# PCB_PCB_NFC-Llamacard_2024-08-03.net
KiCad netlist of a schematic drawn in EasyEDA
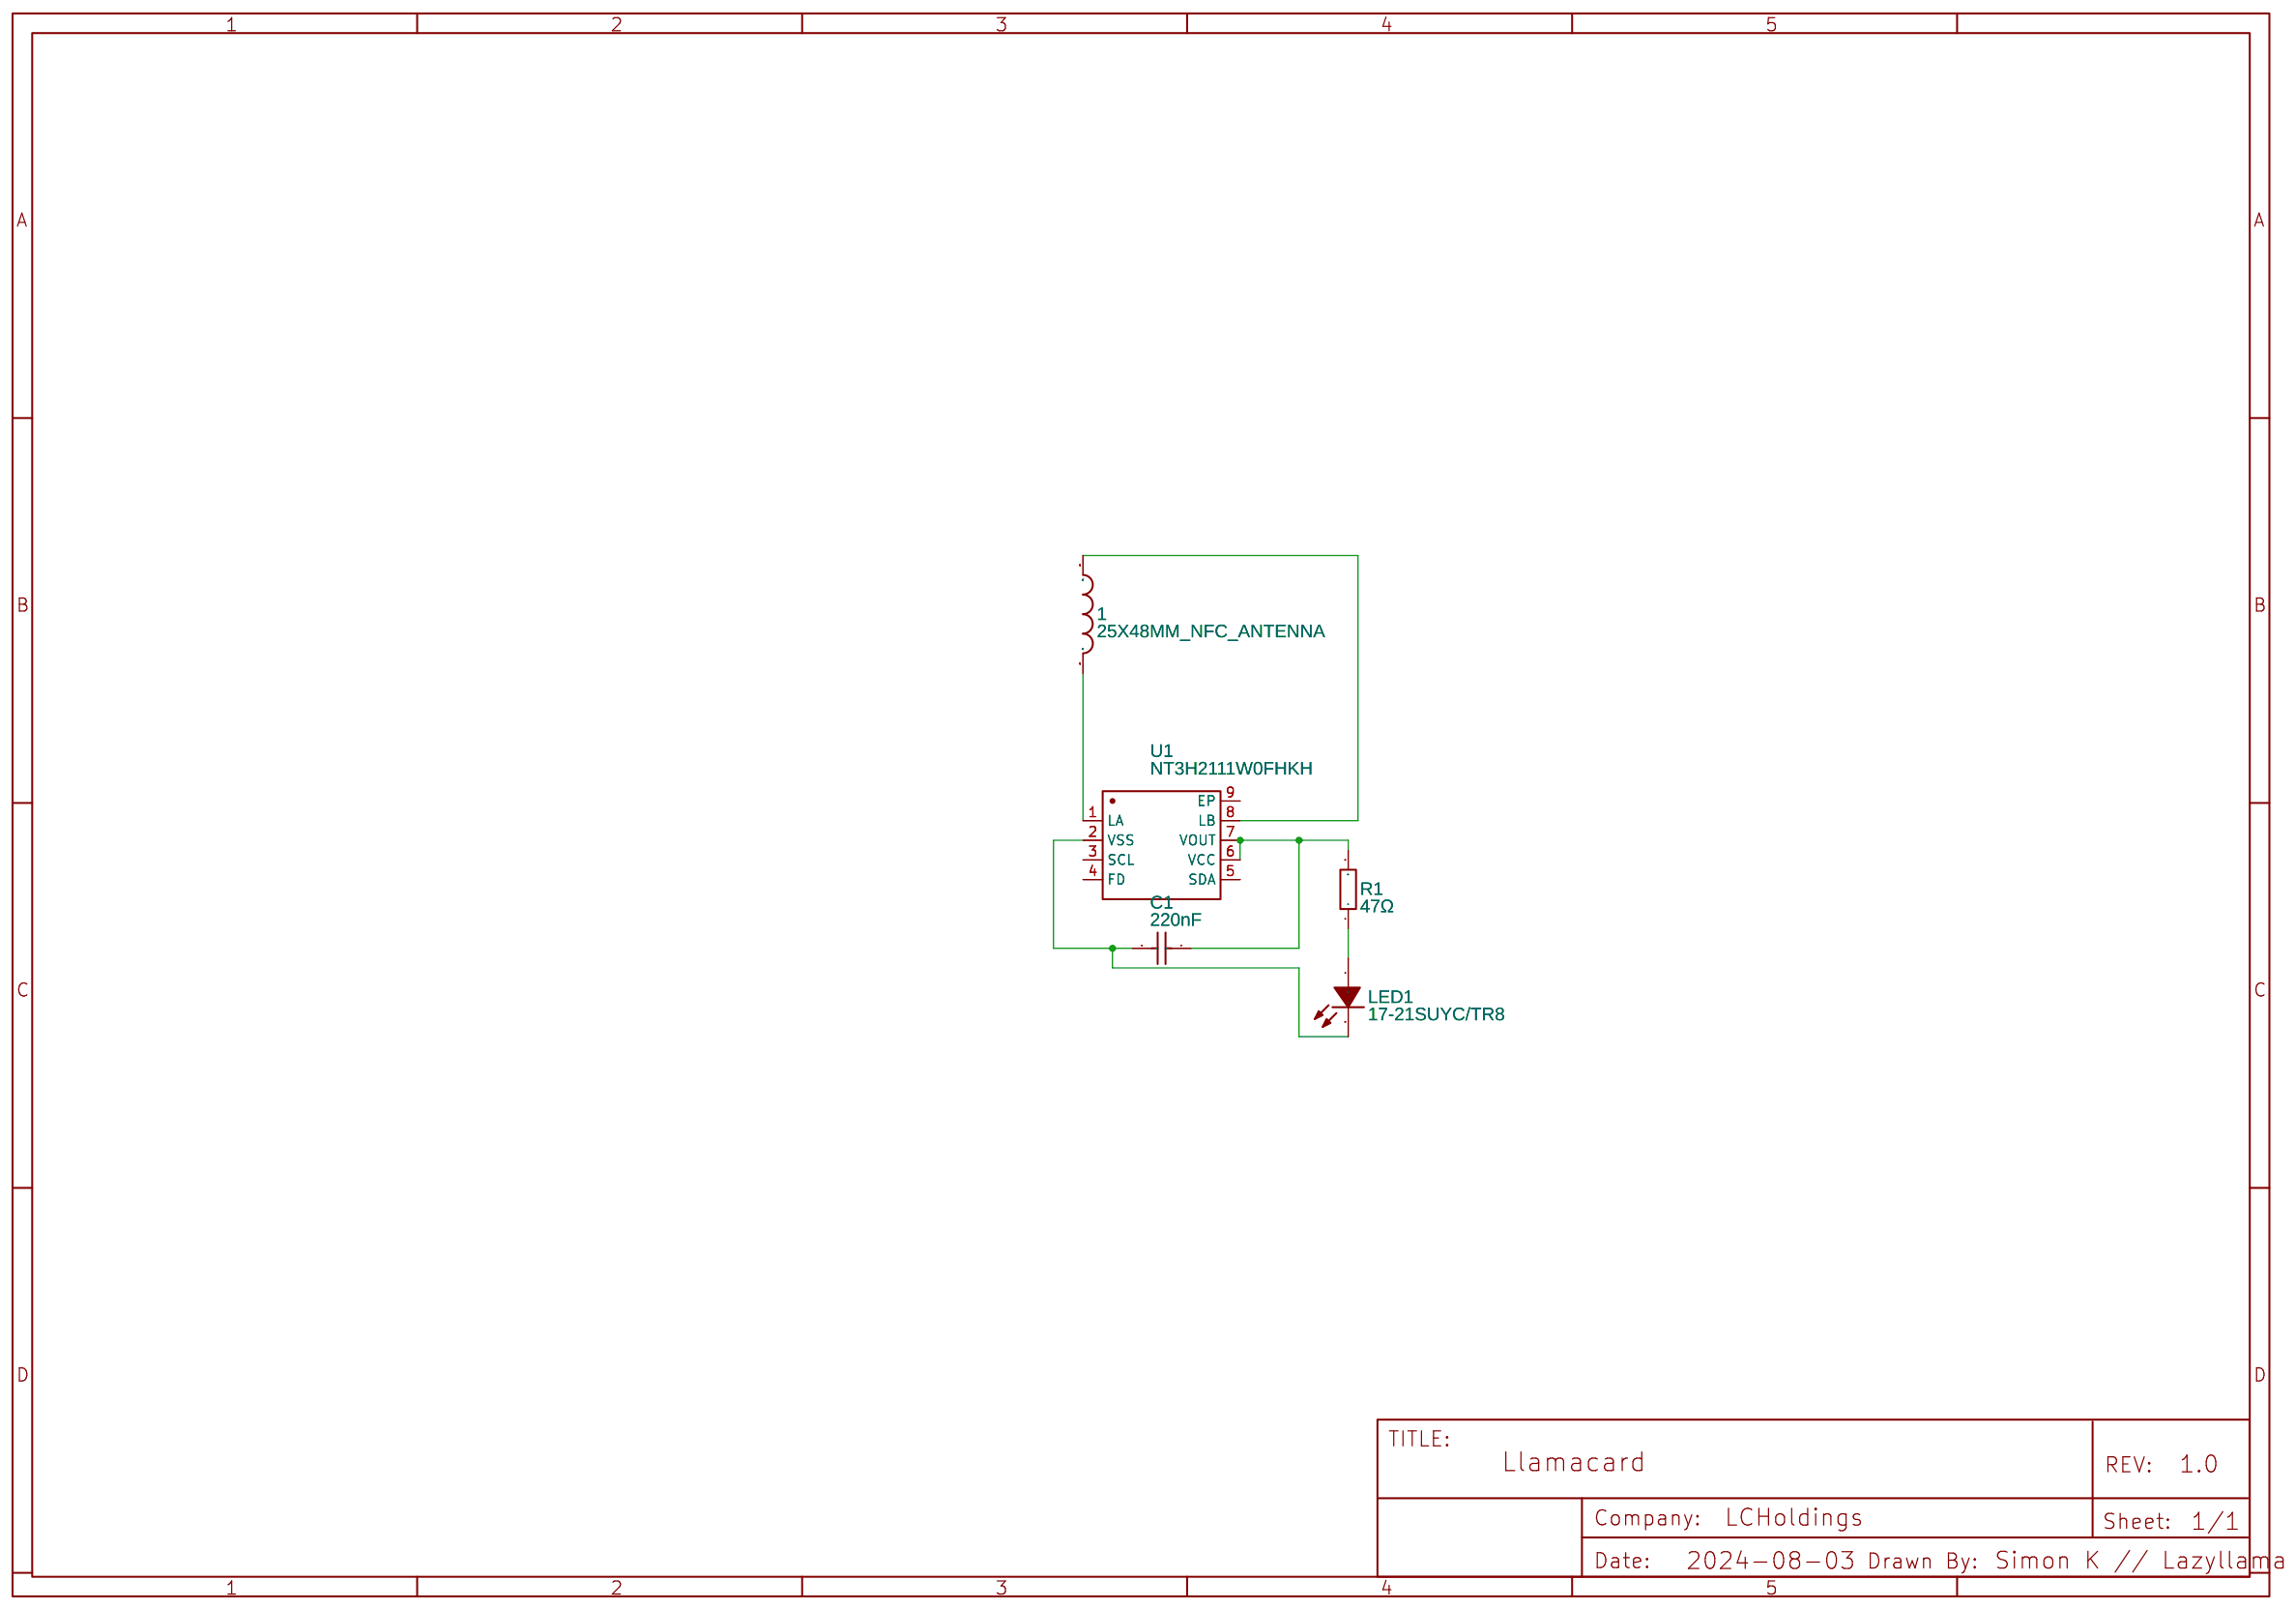
[diagram p0: schematic sheet]

(export (version "E")
  (design (tool "Eeschema 10.0.6"))
  (components
    (comp (ref "1") (value "25X48MM_NFC_ANTENNA") (libsource (lib "") (part "25X48MM_NFC_ANTENNA")))
    (comp (ref "C1")
      (value "220nF")
      (fields
        (field (name "Manufacturer Part") "CL10B224KA8NNNC")
        (field (name "Manufacturer") "SAMSUNG(三星)")
      )
      (libsource (lib "") (part "CL10B224KA8NNNC"))
    )
    (comp (ref "LED1")
      (value "17-21SUYC/TR8")
      (fields (field (name "Manufacturer Part") "KT-0805黄灯") (field (name "Manufacturer") "KENTO"))
      (libsource (lib "") (part "17-21SUYC/TR8"))
    )
    (comp (ref "R1")
      (value "47Ω")
      (fields
        (field (name "Manufacturer Part") "0603WAF470JT5E")
        (field (name "Manufacturer") "UNI-ROYAL(厚声)")
      )
      (libsource (lib "") (part "0603WAF470JT5E"))
    )
    (comp (ref "U1")
      (value "NT3H2111W0FHKH")
      (fields (field (name "Manufacturer") "NXP(恩智浦)"))
      (libsource (lib "") (part "NT3H2111W0FHKH"))
    )
  )
  (nets
    (net (code "1") (name "Net-(LED1-+)") (class "Default")
      (node (ref "LED1") (pin "1") (pinfunction "+_1") (pintype "unspecified"))
      (node (ref "R1") (pin "1") (pinfunction "1_1") (pintype "input"))
    )
    (net (code "2") (name "Net-(LED1--)") (class "Default")
      (node (ref "C1") (pin "2") (pinfunction "2_2") (pintype "input"))
      (node (ref "LED1") (pin "2") (pinfunction "-_2") (pintype "unspecified"))
      (node (ref "U1") (pin "2") (pinfunction "VSS_2") (pintype "unspecified"))
    )
    (net (code "3") (name "Net-(U1-LA)") (class "Default")
      (node (ref "1") (pin "P$2") (pinfunction "P$2_P$2") (pintype "bidirectional"))
      (node (ref "U1") (pin "1") (pinfunction "LA_1") (pintype "unspecified"))
    )
    (net (code "4") (name "Net-(U1-LB)") (class "Default")
      (node (ref "1") (pin "P$1") (pinfunction "P$1_P$1") (pintype "bidirectional"))
      (node (ref "U1") (pin "8") (pinfunction "LB_8") (pintype "unspecified"))
    )
    (net (code "5") (name "Net-(U1-VCC)") (class "Default")
      (node (ref "C1") (pin "1") (pinfunction "1_1") (pintype "input"))
      (node (ref "R1") (pin "2") (pinfunction "2_2") (pintype "input"))
      (node (ref "U1") (pin "6") (pinfunction "VCC_6") (pintype "unspecified"))
      (node (ref "U1") (pin "7") (pinfunction "VOUT_7") (pintype "unspecified"))
    )
    (net (code "6") (name "unconnected-(U1-EP-Pad9)") (class "Default")
      (node (ref "U1") (pin "9") (pinfunction "EP_9") (pintype "unspecified"))
    )
    (net (code "7") (name "unconnected-(U1-FD-Pad4)") (class "Default")
      (node (ref "U1") (pin "4") (pinfunction "FD_4") (pintype "unspecified"))
    )
    (net (code "8") (name "unconnected-(U1-SCL-Pad3)") (class "Default")
      (node (ref "U1") (pin "3") (pinfunction "SCL_3") (pintype "unspecified"))
    )
    (net (code "9") (name "unconnected-(U1-SDA-Pad5)") (class "Default")
      (node (ref "U1") (pin "5") (pinfunction "SDA_5") (pintype "unspecified"))
    )
  )
)
